# PDB2019.net
KiCad netlist of a schematic drawn in EAGLE
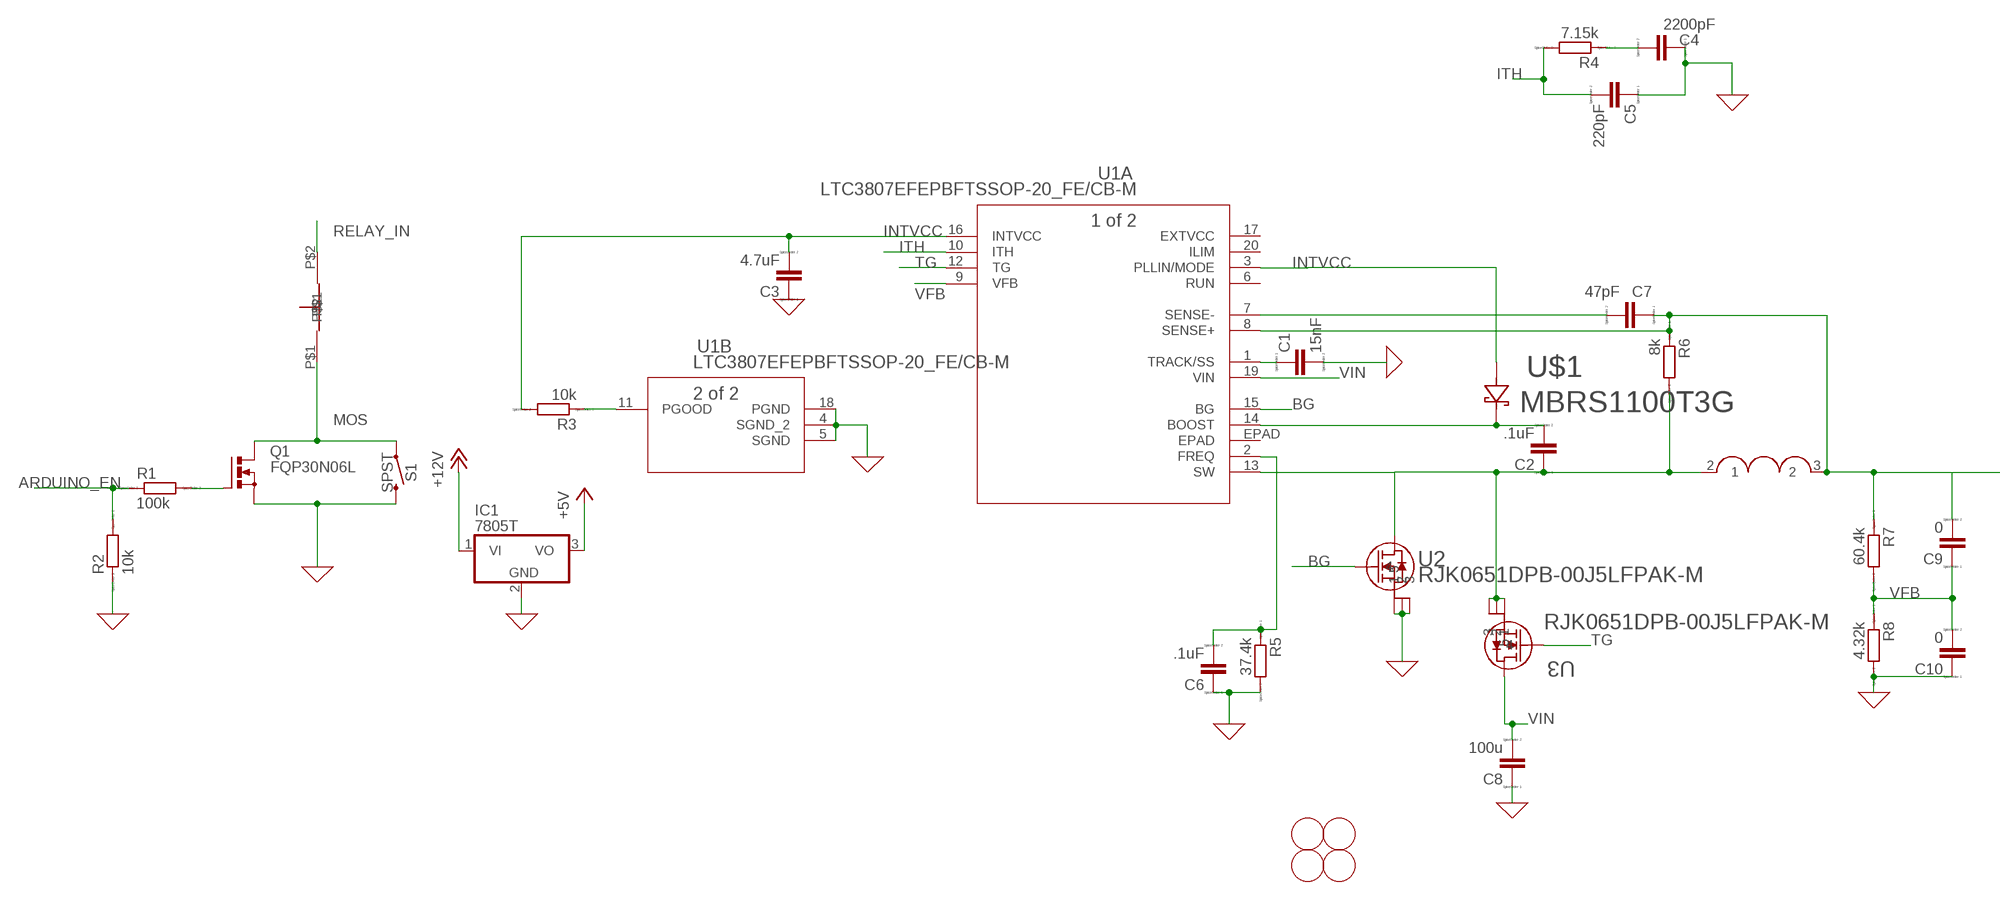
[diagram p0: schematic, sheet 1, part 1 of 2]
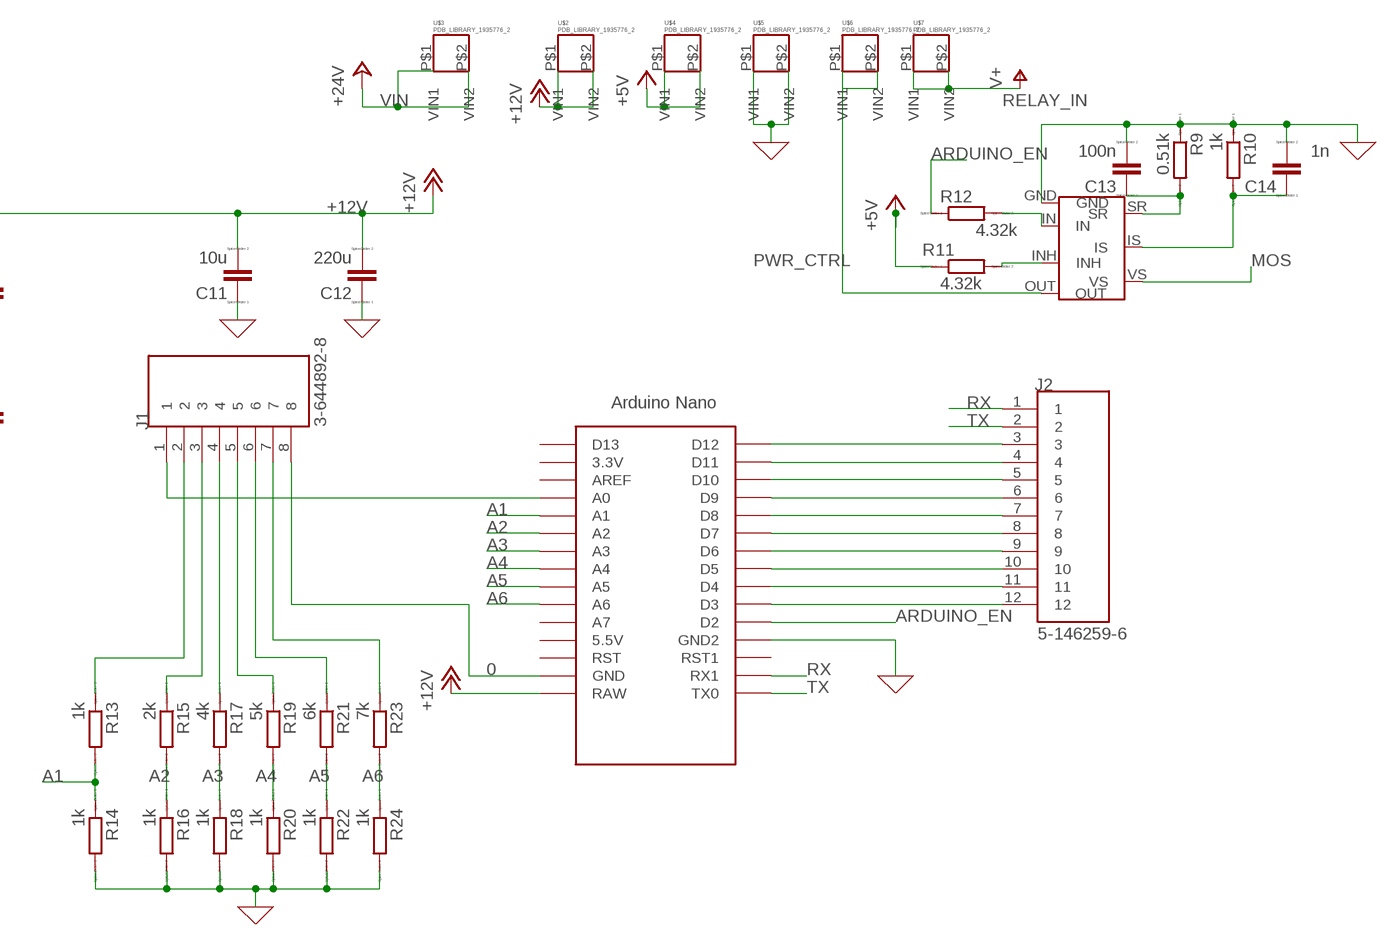
[diagram p1: schematic, sheet 1, part 2 of 2]

(export (version "E")
  (design (tool "Eeschema 10.0.6"))
  (components
    (comp (ref "C1")
      (value "15nF")
      (footprint "eagle-import:C1206")
      (libsource (lib "eagle-import") (part "CC1206"))
    )
    (comp (ref "C2")
      (value ".1uF")
      (footprint "eagle-import:C1206")
      (libsource (lib "eagle-import") (part "CC1206"))
    )
    (comp (ref "C3")
      (value "4.7uF")
      (footprint "eagle-import:C1206")
      (libsource (lib "eagle-import") (part "CC1206"))
    )
    (comp (ref "C4")
      (value "2200pF")
      (footprint "eagle-import:C1206")
      (libsource (lib "eagle-import") (part "CC1206"))
    )
    (comp (ref "C5")
      (value "220pF")
      (footprint "eagle-import:C1206")
      (libsource (lib "eagle-import") (part "CC1206"))
    )
    (comp (ref "C6")
      (value ".1uF")
      (footprint "eagle-import:C1206")
      (libsource (lib "eagle-import") (part "CC1206"))
    )
    (comp (ref "C7")
      (value "47pF")
      (footprint "eagle-import:C1206")
      (libsource (lib "eagle-import") (part "CC1206"))
    )
    (comp (ref "C8")
      (value "100u")
      (footprint "eagle-import:C1206")
      (libsource (lib "eagle-import") (part "CC1206"))
    )
    (comp (ref "C9")
      (value "0")
      (footprint "eagle-import:C1206")
      (libsource (lib "eagle-import") (part "CC1206"))
    )
    (comp (ref "C10")
      (value "0")
      (footprint "eagle-import:C1206")
      (libsource (lib "eagle-import") (part "CC1206"))
    )
    (comp (ref "C11")
      (value "10u")
      (footprint "eagle-import:C1206")
      (libsource (lib "eagle-import") (part "CC1206"))
    )
    (comp (ref "C12")
      (value "220u")
      (footprint "eagle-import:C1206")
      (libsource (lib "eagle-import") (part "CC1206"))
    )
    (comp (ref "C13")
      (value "100n")
      (footprint "eagle-import:C1206")
      (libsource (lib "eagle-import") (part "CC1206"))
    )
    (comp (ref "C14")
      (value "1n")
      (footprint "eagle-import:C1206")
      (libsource (lib "eagle-import") (part "CC1206"))
    )
    (comp (ref "IC1")
      (value "7805T")
      (footprint "eagle-import:TO220H")
      (libsource (lib "eagle-import") (part "78T05"))
    )
    (comp (ref "J1")
      (value "3-644892-8")
      (footprint "eagle-import:TE_3-644892-8")
      (fields (field (name "DIGI-KEY_PART_NUMBER") "A108137-ND") (field (name "MF") "TE Connectivity"))
      (libsource (lib "eagle-import") (part "3-644892-8"))
    )
    (comp (ref "J2")
      (value "5-146259-6")
      (footprint "eagle-import:TE_5-146259-6")
      (fields (field (name "DIGI-KEY_PART_NUMBER") "5-146259-6-ND") (field (name "MF") "TE Connectivity"))
      (libsource (lib "eagle-import") (part "5-146259-6"))
    )
    (comp (ref "L1")
      (value "INDUCT_MOONROCK")
      (footprint "eagle-import:INDUCT_MOONROCK")
      (libsource (lib "eagle-import") (part "INDUCT_MOONROCK"))
    )
    (comp (ref "Q1")
      (value "FQP30N06L")
      (footprint "eagle-import:TO220BV")
      (libsource (lib "eagle-import") (part "BUZ11BV"))
    )
    (comp (ref "R1")
      (value "100k")
      (footprint "eagle-import:0207_10")
      (libsource (lib "eagle-import") (part "R0207/10"))
    )
    (comp (ref "R2")
      (value "10k")
      (footprint "eagle-import:0207_10")
      (libsource (lib "eagle-import") (part "R0207/10"))
    )
    (comp (ref "R3")
      (value "10k")
      (footprint "eagle-import:0207_10")
      (libsource (lib "eagle-import") (part "R0207/10"))
    )
    (comp (ref "R4")
      (value "7.15k")
      (footprint "eagle-import:R1210")
      (libsource (lib "eagle-import") (part "RR1210"))
    )
    (comp (ref "R5")
      (value "37.4k")
      (footprint "eagle-import:R1210")
      (libsource (lib "eagle-import") (part "RR1210"))
    )
    (comp (ref "R6")
      (value "8k")
      (footprint "eagle-import:R1210")
      (libsource (lib "eagle-import") (part "RR1210"))
    )
    (comp (ref "R7")
      (value "60.4k")
      (footprint "eagle-import:R1210")
      (libsource (lib "eagle-import") (part "RR1210"))
    )
    (comp (ref "R8")
      (value "4.32k")
      (footprint "eagle-import:R1210")
      (libsource (lib "eagle-import") (part "RR1210"))
    )
    (comp (ref "R9")
      (value "0.51k")
      (footprint "eagle-import:R1210")
      (libsource (lib "eagle-import") (part "RR1210"))
    )
    (comp (ref "R10")
      (value "1k")
      (footprint "eagle-import:R1210")
      (libsource (lib "eagle-import") (part "RR1210"))
    )
    (comp (ref "R11")
      (value "4.32k")
      (footprint "eagle-import:R1210")
      (libsource (lib "eagle-import") (part "RR1210"))
    )
    (comp (ref "R12")
      (value "4.32k")
      (footprint "eagle-import:R1210")
      (libsource (lib "eagle-import") (part "RR1210"))
    )
    (comp (ref "R13")
      (value "1k")
      (footprint "eagle-import:R1210")
      (libsource (lib "eagle-import") (part "RR1210"))
    )
    (comp (ref "R14")
      (value "1k")
      (footprint "eagle-import:R1210")
      (libsource (lib "eagle-import") (part "RR1210"))
    )
    (comp (ref "R15")
      (value "2k")
      (footprint "eagle-import:R1210")
      (libsource (lib "eagle-import") (part "RR1210"))
    )
    (comp (ref "R16")
      (value "1k")
      (footprint "eagle-import:R1210")
      (libsource (lib "eagle-import") (part "RR1210"))
    )
    (comp (ref "R17")
      (value "4k")
      (footprint "eagle-import:R1210")
      (libsource (lib "eagle-import") (part "RR1210"))
    )
    (comp (ref "R18")
      (value "1k")
      (footprint "eagle-import:R1210")
      (libsource (lib "eagle-import") (part "RR1210"))
    )
    (comp (ref "R19")
      (value "5k")
      (footprint "eagle-import:R1210")
      (libsource (lib "eagle-import") (part "RR1210"))
    )
    (comp (ref "R20")
      (value "1k")
      (footprint "eagle-import:R1210")
      (libsource (lib "eagle-import") (part "RR1210"))
    )
    (comp (ref "R21")
      (value "6k")
      (footprint "eagle-import:R1210")
      (libsource (lib "eagle-import") (part "RR1210"))
    )
    (comp (ref "R22")
      (value "1k")
      (footprint "eagle-import:R1210")
      (libsource (lib "eagle-import") (part "RR1210"))
    )
    (comp (ref "R23")
      (value "7k")
      (footprint "eagle-import:R1210")
      (libsource (lib "eagle-import") (part "RR1210"))
    )
    (comp (ref "R24")
      (value "1k")
      (footprint "eagle-import:R1210")
      (libsource (lib "eagle-import") (part "RR1210"))
    )
    (comp (ref "S1")
      (value "SPST")
      (footprint "eagle-import:TACTILE_SWITCH_PTH_6.0MM_KIT")
      (libsource (lib "eagle-import") (part "MOMENTARY-SWITCH-SPST-PTH-6.0MM-KIT"))
    )
    (comp (ref "SW1")
      (value "SPSTSWITCH")
      (footprint "eagle-import:2HOLES")
      (libsource (lib "eagle-import") (part "SPSTSWITCH"))
    )
    (comp (ref "U$1")
      (value "MBRS1100T3G")
      (footprint "eagle-import:SMB")
      (libsource (lib "eagle-import") (part "MBRS1100T3G"))
    )
    (comp (ref "U$2")
      (value "PDB_LIBRARY_1935776_2")
      (footprint "eagle-import:PDB_LIBRARY_PT2,5_2-5,0-H_2")
      (libsource (lib "eagle-import") (part "PDB_LIBRARY_1935776_2"))
    )
    (comp (ref "U$3")
      (value "PDB_LIBRARY_1935776_2")
      (footprint "eagle-import:PDB_LIBRARY_PT2,5_2-5,0-H_2")
      (libsource (lib "eagle-import") (part "PDB_LIBRARY_1935776_2"))
    )
    (comp (ref "U$4")
      (value "PDB_LIBRARY_1935776_2")
      (footprint "eagle-import:PDB_LIBRARY_PT2,5_2-5,0-H_2")
      (libsource (lib "eagle-import") (part "PDB_LIBRARY_1935776_2"))
    )
    (comp (ref "U$5")
      (value "PDB_LIBRARY_1935776_2")
      (footprint "eagle-import:PDB_LIBRARY_PT2,5_2-5,0-H_2")
      (libsource (lib "eagle-import") (part "PDB_LIBRARY_1935776_2"))
    )
    (comp (ref "U$6")
      (value "PDB_LIBRARY_1935776_2")
      (footprint "eagle-import:PDB_LIBRARY_PT2,5_2-5,0-H_2")
      (libsource (lib "eagle-import") (part "PDB_LIBRARY_1935776_2"))
    )
    (comp (ref "U$7")
      (value "PDB_LIBRARY_1935776_2")
      (footprint "eagle-import:PDB_LIBRARY_PT2,5_2-5,0-H_2")
      (libsource (lib "eagle-import") (part "PDB_LIBRARY_1935776_2"))
    )
    (comp (ref "U$8")
      (value "NANO")
      (footprint "eagle-import:NANO")
      (libsource (lib "eagle-import") (part "NANO"))
    )
    (comp (ref "U$9")
      (value "MOUNTINGHOLES")
      (footprint "eagle-import:MOUNTINGHOLES")
      (libsource (lib "eagle-import") (part "MOUNTINGHOLES"))
    )
    (comp (ref "U1")
      (value "LTC3807EFEPBFTSSOP-20_FE/CB-M")
      (footprint "eagle-import:TSSOP-20_FE_CB-M")
      (fields (field (name "MANUFACTURER_PART_NUMBER") "LTC3807EFE#PBF"))
      (libsource (lib "eagle-import") (part "LTC3807EFEPBFTSSOP-20_FE/CB-M"))
    )
    (comp (ref "U2")
      (value "RJK0651DPB-00J5LFPAK-M")
      (footprint "eagle-import:LFPAK-M")
      (fields (field (name "MANUFACTURER_PART_NUMBER") "RJK0651DPB00#J5"))
      (libsource (lib "eagle-import") (part "RJK0651DPB-00J5LFPAK-M"))
    )
    (comp (ref "U3")
      (value "RJK0651DPB-00J5LFPAK-M")
      (footprint "eagle-import:LFPAK-M")
      (fields (field (name "MANUFACTURER_PART_NUMBER") "RJK0651DPB00#J5"))
      (libsource (lib "eagle-import") (part "RJK0651DPB-00J5LFPAK-M"))
    )
    (comp (ref "U4")
      (value "BTN8982TA")
      (footprint "eagle-import:TO-263-8")
      (libsource (lib "eagle-import") (part "BTN8982TA"))
    )
  )
  (nets
    (net (code "1") (name "+5V") (class "Default")
      (node (ref "IC1") (pin "3") (pinfunction "VO_3") (pintype "passive"))
      (node (ref "R11") (pin "1") (pinfunction "1_1") (pintype "passive"))
      (node (ref "U$4") (pin "P$1") (pinfunction "VIN1_P$1") (pintype "bidirectional"))
      (node (ref "U$4") (pin "P$2") (pinfunction "VIN2_P$2") (pintype "bidirectional"))
    )
    (net (code "2") (name "+12V") (class "Default")
      (node (ref "C11") (pin "2") (pinfunction "2_2") (pintype "passive"))
      (node (ref "C12") (pin "2") (pinfunction "2_2") (pintype "passive"))
      (node (ref "C7") (pin "1") (pinfunction "1_1") (pintype "passive"))
      (node (ref "C9") (pin "2") (pinfunction "2_2") (pintype "passive"))
      (node (ref "IC1") (pin "1") (pinfunction "VI_1") (pintype "input"))
      (node (ref "L1") (pin "3") (pinfunction "2_3") (pintype "bidirectional"))
      (node (ref "R6") (pin "1") (pinfunction "1_1") (pintype "passive"))
      (node (ref "R7") (pin "1") (pinfunction "1_1") (pintype "passive"))
      (node (ref "U$2") (pin "P$1") (pinfunction "VIN1_P$1") (pintype "bidirectional"))
      (node (ref "U$2") (pin "P$2") (pinfunction "VIN2_P$2") (pintype "bidirectional"))
      (node (ref "U$8") (pin "RAW") (pinfunction "RAW_RAW") (pintype "bidirectional"))
      (node (ref "U1") (pin "8") (pinfunction "SENSE+_8") (pintype "input"))
    )
    (net (code "3") (name "+24V") (class "Default")
      (node (ref "C8") (pin "2") (pinfunction "2_2") (pintype "passive"))
      (node (ref "U$3") (pin "P$1") (pinfunction "VIN1_P$1") (pintype "bidirectional"))
      (node (ref "U$3") (pin "P$2") (pinfunction "VIN2_P$2") (pintype "bidirectional"))
      (node (ref "U1") (pin "19") (pinfunction "VIN_19") (pintype "input"))
      (node (ref "U3") (pin "5") (pinfunction "5_5") (pintype "passive"))
    )
    (net (code "4") (name "/A1") (class "Default")
      (node (ref "R13") (pin "2") (pinfunction "2_2") (pintype "passive"))
      (node (ref "R14") (pin "1") (pinfunction "1_1") (pintype "passive"))
      (node (ref "U$8") (pin "A1") (pinfunction "A1_A1") (pintype "bidirectional"))
    )
    (net (code "5") (name "/A2") (class "Default")
      (node (ref "R15") (pin "2") (pinfunction "2_2") (pintype "passive"))
      (node (ref "R16") (pin "1") (pinfunction "1_1") (pintype "passive"))
      (node (ref "U$8") (pin "A2") (pinfunction "A2_A2") (pintype "bidirectional"))
    )
    (net (code "6") (name "/A3") (class "Default")
      (node (ref "R17") (pin "2") (pinfunction "2_2") (pintype "passive"))
      (node (ref "R18") (pin "1") (pinfunction "1_1") (pintype "passive"))
      (node (ref "U$8") (pin "A3") (pinfunction "A3_A3") (pintype "bidirectional"))
    )
    (net (code "7") (name "/A4") (class "Default")
      (node (ref "R19") (pin "2") (pinfunction "2_2") (pintype "passive"))
      (node (ref "R20") (pin "1") (pinfunction "1_1") (pintype "passive"))
      (node (ref "U$8") (pin "A4") (pinfunction "A4_A4") (pintype "bidirectional"))
    )
    (net (code "8") (name "/A5") (class "Default")
      (node (ref "R21") (pin "2") (pinfunction "2_2") (pintype "passive"))
      (node (ref "R22") (pin "1") (pinfunction "1_1") (pintype "passive"))
      (node (ref "U$8") (pin "A5") (pinfunction "A5_A5") (pintype "bidirectional"))
    )
    (net (code "9") (name "/A6") (class "Default")
      (node (ref "R23") (pin "2") (pinfunction "2_2") (pintype "passive"))
      (node (ref "R24") (pin "1") (pinfunction "1_1") (pintype "passive"))
      (node (ref "U$8") (pin "A6") (pinfunction "A6_A6") (pintype "bidirectional"))
    )
    (net (code "10") (name "/ARDUINO_EN") (class "Default")
      (node (ref "R1") (pin "1") (pinfunction "1_1") (pintype "passive"))
      (node (ref "R12") (pin "1") (pinfunction "1_1") (pintype "passive"))
      (node (ref "R2") (pin "2") (pinfunction "2_2") (pintype "passive"))
      (node (ref "U$8") (pin "D2") (pinfunction "D2_D2") (pintype "bidirectional"))
    )
    (net (code "11") (name "/BG") (class "Default")
      (node (ref "U1") (pin "15") (pinfunction "BG_15") (pintype "passive"))
      (node (ref "U2") (pin "4") (pinfunction "4_4") (pintype "passive"))
    )
    (net (code "12") (name "/INTVCC") (class "Default")
      (node (ref "C3") (pin "2") (pinfunction "2_2") (pintype "passive"))
      (node (ref "R3") (pin "2") (pinfunction "2_2") (pintype "passive"))
      (node (ref "U$1") (pin "2") (pinfunction "2_2") (pintype "passive"))
      (node (ref "U1") (pin "16") (pinfunction "INTVCC_16") (pintype "output"))
      (node (ref "U1") (pin "3") (pinfunction "PLLIN/MODE_3") (pintype "input"))
    )
    (net (code "13") (name "/ITH") (class "Default")
      (node (ref "C5") (pin "2") (pinfunction "2_2") (pintype "passive"))
      (node (ref "R4") (pin "2") (pinfunction "2_2") (pintype "passive"))
      (node (ref "U1") (pin "10") (pinfunction "ITH_10") (pintype "output"))
    )
    (net (code "14") (name "/MOS") (class "Default")
      (node (ref "Q1") (pin "D") (pinfunction "D_D") (pintype "passive"))
      (node (ref "S1") (pin "1") (pinfunction "1_1") (pintype "passive"))
      (node (ref "SW1") (pin "P$1") (pinfunction "P$1_P$1") (pintype "bidirectional"))
      (node (ref "U4") (pin "VS") (pinfunction "VS_VS") (pintype "bidirectional"))
    )
    (net (code "15") (name "/PWR_CTRL") (class "Default")
      (node (ref "U$6") (pin "P$1") (pinfunction "VIN1_P$1") (pintype "bidirectional"))
      (node (ref "U$6") (pin "P$2") (pinfunction "VIN2_P$2") (pintype "bidirectional"))
      (node (ref "U4") (pin "OUT") (pinfunction "OUT_OUT") (pintype "bidirectional"))
    )
    (net (code "16") (name "/RX") (class "Default")
      (node (ref "J2") (pin "1") (pinfunction "1_1") (pintype "passive"))
      (node (ref "U$8") (pin "RX1") (pinfunction "RX1_RX1") (pintype "bidirectional"))
    )
    (net (code "17") (name "/TG") (class "Default")
      (node (ref "U1") (pin "12") (pinfunction "TG_12") (pintype "output"))
      (node (ref "U3") (pin "4") (pinfunction "4_4") (pintype "passive"))
    )
    (net (code "18") (name "/TX") (class "Default")
      (node (ref "J2") (pin "2") (pinfunction "2_2") (pintype "passive"))
      (node (ref "U$8") (pin "TX0") (pinfunction "TX0_TX0") (pintype "bidirectional"))
    )
    (net (code "19") (name "/VFB") (class "Default")
      (node (ref "C10") (pin "2") (pinfunction "2_2") (pintype "passive"))
      (node (ref "C9") (pin "1") (pinfunction "1_1") (pintype "passive"))
      (node (ref "R7") (pin "2") (pinfunction "2_2") (pintype "passive"))
      (node (ref "R8") (pin "1") (pinfunction "1_1") (pintype "passive"))
      (node (ref "U1") (pin "9") (pinfunction "VFB_9") (pintype "output"))
    )
    (net (code "20") (name "GND") (class "Default")
      (node (ref "C1") (pin "2") (pinfunction "2_2") (pintype "passive"))
      (node (ref "C10") (pin "1") (pinfunction "1_1") (pintype "passive"))
      (node (ref "C11") (pin "1") (pinfunction "1_1") (pintype "passive"))
      (node (ref "C12") (pin "1") (pinfunction "1_1") (pintype "passive"))
      (node (ref "C13") (pin "2") (pinfunction "2_2") (pintype "passive"))
      (node (ref "C14") (pin "2") (pinfunction "2_2") (pintype "passive"))
      (node (ref "C3") (pin "1") (pinfunction "1_1") (pintype "passive"))
      (node (ref "C4") (pin "1") (pinfunction "1_1") (pintype "passive"))
      (node (ref "C5") (pin "1") (pinfunction "1_1") (pintype "passive"))
      (node (ref "C6") (pin "1") (pinfunction "1_1") (pintype "passive"))
      (node (ref "C8") (pin "1") (pinfunction "1_1") (pintype "passive"))
      (node (ref "IC1") (pin "2") (pinfunction "GND_2") (pintype "passive"))
      (node (ref "J1") (pin "8") (pinfunction "8_8") (pintype "passive"))
      (node (ref "Q1") (pin "S") (pinfunction "S_S") (pintype "passive"))
      (node (ref "R10") (pin "1") (pinfunction "1_1") (pintype "passive"))
      (node (ref "R14") (pin "2") (pinfunction "2_2") (pintype "passive"))
      (node (ref "R16") (pin "2") (pinfunction "2_2") (pintype "passive"))
      (node (ref "R18") (pin "2") (pinfunction "2_2") (pintype "passive"))
      (node (ref "R2") (pin "1") (pinfunction "1_1") (pintype "passive"))
      (node (ref "R20") (pin "2") (pinfunction "2_2") (pintype "passive"))
      (node (ref "R22") (pin "2") (pinfunction "2_2") (pintype "passive"))
      (node (ref "R24") (pin "2") (pinfunction "2_2") (pintype "passive"))
      (node (ref "R5") (pin "2") (pinfunction "2_2") (pintype "passive"))
      (node (ref "R8") (pin "2") (pinfunction "2_2") (pintype "passive"))
      (node (ref "R9") (pin "1") (pinfunction "1_1") (pintype "passive"))
      (node (ref "S1") (pin "3") (pinfunction "2_3") (pintype "passive"))
      (node (ref "U$5") (pin "P$1") (pinfunction "VIN1_P$1") (pintype "bidirectional"))
      (node (ref "U$5") (pin "P$2") (pinfunction "VIN2_P$2") (pintype "bidirectional"))
      (node (ref "U$8") (pin "GND") (pinfunction "GND_GND") (pintype "bidirectional"))
      (node (ref "U$8") (pin "GND1") (pinfunction "GND2_GND1") (pintype "bidirectional"))
      (node (ref "U1") (pin "18") (pinfunction "PGND_18") (pintype "power_in"))
      (node (ref "U1") (pin "4") (pinfunction "SGND_2_4") (pintype "power_in"))
      (node (ref "U1") (pin "5") (pinfunction "SGND_5") (pintype "power_in"))
      (node (ref "U2") (pin "1") (pinfunction "1_1") (pintype "passive"))
      (node (ref "U2") (pin "2") (pinfunction "2_2") (pintype "passive"))
      (node (ref "U2") (pin "3") (pinfunction "3_3") (pintype "passive"))
      (node (ref "U4") (pin "GND") (pinfunction "GND_GND") (pintype "bidirectional"))
    )
    (net (code "21") (name "Net-(C4-Pad2)") (class "Default")
      (node (ref "C4") (pin "2") (pinfunction "2_2") (pintype "passive"))
      (node (ref "R4") (pin "1") (pinfunction "1_1") (pintype "passive"))
    )
    (net (code "22") (name "Net-(C13-Pad1)") (class "Default")
      (node (ref "C13") (pin "1") (pinfunction "1_1") (pintype "passive"))
      (node (ref "R9") (pin "2") (pinfunction "2_2") (pintype "passive"))
      (node (ref "U4") (pin "SR") (pinfunction "SR_SR") (pintype "bidirectional"))
    )
    (net (code "23") (name "Net-(C14-Pad1)") (class "Default")
      (node (ref "C14") (pin "1") (pinfunction "1_1") (pintype "passive"))
      (node (ref "R10") (pin "2") (pinfunction "2_2") (pintype "passive"))
      (node (ref "U4") (pin "IS") (pinfunction "IS_IS") (pintype "bidirectional"))
    )
    (net (code "24") (name "Net-(J1-Pad1)") (class "Default")
      (node (ref "J1") (pin "1") (pinfunction "1_1") (pintype "passive"))
      (node (ref "U$8") (pin "A0") (pinfunction "A0_A0") (pintype "bidirectional"))
    )
    (net (code "25") (name "Net-(J1-Pad2)") (class "Default")
      (node (ref "J1") (pin "2") (pinfunction "2_2") (pintype "passive"))
      (node (ref "R13") (pin "1") (pinfunction "1_1") (pintype "passive"))
    )
    (net (code "26") (name "Net-(J1-Pad3)") (class "Default")
      (node (ref "J1") (pin "3") (pinfunction "3_3") (pintype "passive"))
      (node (ref "R15") (pin "1") (pinfunction "1_1") (pintype "passive"))
    )
    (net (code "27") (name "Net-(J1-Pad4)") (class "Default")
      (node (ref "J1") (pin "4") (pinfunction "4_4") (pintype "passive"))
      (node (ref "R17") (pin "1") (pinfunction "1_1") (pintype "passive"))
    )
    (net (code "28") (name "Net-(J1-Pad5)") (class "Default")
      (node (ref "J1") (pin "5") (pinfunction "5_5") (pintype "passive"))
      (node (ref "R19") (pin "1") (pinfunction "1_1") (pintype "passive"))
    )
    (net (code "29") (name "Net-(J1-Pad6)") (class "Default")
      (node (ref "J1") (pin "6") (pinfunction "6_6") (pintype "passive"))
      (node (ref "R21") (pin "1") (pinfunction "1_1") (pintype "passive"))
    )
    (net (code "30") (name "Net-(J1-Pad7)") (class "Default")
      (node (ref "J1") (pin "7") (pinfunction "7_7") (pintype "passive"))
      (node (ref "R23") (pin "1") (pinfunction "1_1") (pintype "passive"))
    )
    (net (code "31") (name "Net-(J2-Pad3)") (class "Default")
      (node (ref "J2") (pin "3") (pinfunction "3_3") (pintype "passive"))
      (node (ref "U$8") (pin "D12") (pinfunction "D12_D12") (pintype "bidirectional"))
    )
    (net (code "32") (name "Net-(J2-Pad4)") (class "Default")
      (node (ref "J2") (pin "4") (pinfunction "4_4") (pintype "passive"))
      (node (ref "U$8") (pin "D11") (pinfunction "D11_D11") (pintype "bidirectional"))
    )
    (net (code "33") (name "Net-(J2-Pad5)") (class "Default")
      (node (ref "J2") (pin "5") (pinfunction "5_5") (pintype "passive"))
      (node (ref "U$8") (pin "D10") (pinfunction "D10_D10") (pintype "bidirectional"))
    )
    (net (code "34") (name "Net-(J2-Pad6)") (class "Default")
      (node (ref "J2") (pin "6") (pinfunction "6_6") (pintype "passive"))
      (node (ref "U$8") (pin "D9") (pinfunction "D9_D9") (pintype "bidirectional"))
    )
    (net (code "35") (name "Net-(J2-Pad7)") (class "Default")
      (node (ref "J2") (pin "7") (pinfunction "7_7") (pintype "passive"))
      (node (ref "U$8") (pin "D8") (pinfunction "D8_D8") (pintype "bidirectional"))
    )
    (net (code "36") (name "Net-(J2-Pad8)") (class "Default")
      (node (ref "J2") (pin "8") (pinfunction "8_8") (pintype "passive"))
      (node (ref "U$8") (pin "D7") (pinfunction "D7_D7") (pintype "bidirectional"))
    )
    (net (code "37") (name "Net-(J2-Pad9)") (class "Default")
      (node (ref "J2") (pin "9") (pinfunction "9_9") (pintype "passive"))
      (node (ref "U$8") (pin "D6") (pinfunction "D6_D6") (pintype "bidirectional"))
    )
    (net (code "38") (name "Net-(J2-Pad10)") (class "Default")
      (node (ref "J2") (pin "10") (pinfunction "10_10") (pintype "passive"))
      (node (ref "U$8") (pin "D5") (pinfunction "D5_D5") (pintype "bidirectional"))
    )
    (net (code "39") (name "Net-(J2-Pad11)") (class "Default")
      (node (ref "J2") (pin "11") (pinfunction "11_11") (pintype "passive"))
      (node (ref "U$8") (pin "D4") (pinfunction "D4_D4") (pintype "bidirectional"))
    )
    (net (code "40") (name "Net-(J2-Pad12)") (class "Default")
      (node (ref "J2") (pin "12") (pinfunction "12_12") (pintype "passive"))
      (node (ref "U$8") (pin "D3") (pinfunction "D3_D3") (pintype "bidirectional"))
    )
    (net (code "41") (name "Net-(L1-1)") (class "Default")
      (node (ref "C2") (pin "1") (pinfunction "1_1") (pintype "passive"))
      (node (ref "L1") (pin "2") (pinfunction "1_2") (pintype "bidirectional"))
      (node (ref "R6") (pin "2") (pinfunction "2_2") (pintype "passive"))
      (node (ref "U1") (pin "13") (pinfunction "SW_13") (pintype "passive"))
      (node (ref "U2") (pin "5") (pinfunction "5_5") (pintype "passive"))
      (node (ref "U3") (pin "1") (pinfunction "1_1") (pintype "passive"))
      (node (ref "U3") (pin "2") (pinfunction "2_2") (pintype "passive"))
      (node (ref "U3") (pin "3") (pinfunction "3_3") (pintype "passive"))
    )
    (net (code "42") (name "Net-(Q1-PadG)") (class "Default")
      (node (ref "Q1") (pin "G") (pinfunction "G_G") (pintype "passive"))
      (node (ref "R1") (pin "2") (pinfunction "2_2") (pintype "passive"))
    )
    (net (code "43") (name "Net-(R11-Pad2)") (class "Default")
      (node (ref "R11") (pin "2") (pinfunction "2_2") (pintype "passive"))
      (node (ref "U4") (pin "INH") (pinfunction "INH_INH") (pintype "bidirectional"))
    )
    (net (code "44") (name "Net-(R12-Pad2)") (class "Default")
      (node (ref "R12") (pin "2") (pinfunction "2_2") (pintype "passive"))
      (node (ref "U4") (pin "IN") (pinfunction "IN_IN") (pintype "bidirectional"))
    )
    (net (code "45") (name "Net-(U1A-BOOST)") (class "Default")
      (node (ref "C2") (pin "2") (pinfunction "2_2") (pintype "passive"))
      (node (ref "U$1") (pin "1") (pinfunction "1_1") (pintype "passive"))
      (node (ref "U1") (pin "14") (pinfunction "BOOST_14") (pintype "passive"))
    )
    (net (code "46") (name "Net-(U1A-FREQ)") (class "Default")
      (node (ref "C6") (pin "2") (pinfunction "2_2") (pintype "passive"))
      (node (ref "R5") (pin "1") (pinfunction "1_1") (pintype "passive"))
      (node (ref "U1") (pin "2") (pinfunction "FREQ_2") (pintype "passive"))
    )
    (net (code "47") (name "Net-(U1A-SENSE-)") (class "Default")
      (node (ref "C7") (pin "2") (pinfunction "2_2") (pintype "passive"))
      (node (ref "U1") (pin "7") (pinfunction "SENSE-_7") (pintype "input"))
    )
    (net (code "48") (name "Net-(U1A-TRACK{slash}SS)") (class "Default")
      (node (ref "C1") (pin "1") (pinfunction "1_1") (pintype "passive"))
      (node (ref "U1") (pin "1") (pinfunction "TRACK/SS_1") (pintype "input"))
    )
    (net (code "49") (name "Net-(U1B-PGOOD)") (class "Default")
      (node (ref "R3") (pin "1") (pinfunction "1_1") (pintype "passive"))
      (node (ref "U1") (pin "11") (pinfunction "PGOOD_11") (pintype "output"))
    )
    (net (code "50") (name "V+") (class "Default")
      (node (ref "SW1") (pin "P$2") (pinfunction "P$2_P$2") (pintype "bidirectional"))
      (node (ref "U$7") (pin "P$1") (pinfunction "VIN1_P$1") (pintype "bidirectional"))
      (node (ref "U$7") (pin "P$2") (pinfunction "VIN2_P$2") (pintype "bidirectional"))
    )
    (net (code "51") (name "unconnected-(U$8-5.5V-Pad5V)") (class "Default")
      (node (ref "U$8") (pin "5V") (pinfunction "5.5V_5V") (pintype "bidirectional"))
    )
    (net (code "52") (name "unconnected-(U$8-Pad3.3V)") (class "Default")
      (node (ref "U$8") (pin "3.3V") (pinfunction "3.3V_3.3V") (pintype "bidirectional"))
    )
    (net (code "53") (name "unconnected-(U$8-PadA7)") (class "Default")
      (node (ref "U$8") (pin "A7") (pinfunction "A7_A7") (pintype "bidirectional"))
    )
    (net (code "54") (name "unconnected-(U$8-PadAREF)") (class "Default")
      (node (ref "U$8") (pin "AREF") (pinfunction "AREF_AREF") (pintype "bidirectional"))
    )
    (net (code "55") (name "unconnected-(U$8-PadD13)") (class "Default")
      (node (ref "U$8") (pin "D13") (pinfunction "D13_D13") (pintype "bidirectional"))
    )
    (net (code "56") (name "unconnected-(U$8-PadICSP1)") (class "Default")
      (node (ref "U$8") (pin "ICSP1") (pinfunction "ICSP1_ICSP1") (pintype "bidirectional"))
    )
    (net (code "57") (name "unconnected-(U$8-PadICSP2)") (class "Default")
      (node (ref "U$8") (pin "ICSP2") (pinfunction "ICSP2_ICSP2") (pintype "bidirectional"))
    )
    (net (code "58") (name "unconnected-(U$8-PadICSP3)") (class "Default")
      (node (ref "U$8") (pin "ICSP3") (pinfunction "ICSP3_ICSP3") (pintype "bidirectional"))
    )
    (net (code "59") (name "unconnected-(U$8-PadICSP4)") (class "Default")
      (node (ref "U$8") (pin "ICSP4") (pinfunction "ICSP4_ICSP4") (pintype "bidirectional"))
    )
    (net (code "60") (name "unconnected-(U$8-PadICSP5)") (class "Default")
      (node (ref "U$8") (pin "ICSP5") (pinfunction "ICSP5_ICSP5") (pintype "bidirectional"))
    )
    (net (code "61") (name "unconnected-(U$8-PadICSP6)") (class "Default")
      (node (ref "U$8") (pin "ICSP6") (pinfunction "ICSP6_ICSP6") (pintype "bidirectional"))
    )
    (net (code "62") (name "unconnected-(U$8-PadRST)") (class "Default")
      (node (ref "U$8") (pin "RST") (pinfunction "RST_RST") (pintype "bidirectional"))
    )
    (net (code "63") (name "unconnected-(U$8-PadRST1)") (class "Default")
      (node (ref "U$8") (pin "RST1") (pinfunction "RST1_RST1") (pintype "bidirectional"))
    )
    (net (code "64") (name "unconnected-(U1-PadEPAD)") (class "Default")
      (node (ref "U1") (pin "EPAD") (pinfunction "EPAD_EPAD") (pintype "passive"))
    )
    (net (code "65") (name "unconnected-(U1A-EXTVCC-Pad17)") (class "Default")
      (node (ref "U1") (pin "17") (pinfunction "EXTVCC_17") (pintype "input"))
    )
    (net (code "66") (name "unconnected-(U1A-ILIM-Pad20)") (class "Default")
      (node (ref "U1") (pin "20") (pinfunction "ILIM_20") (pintype "input"))
    )
    (net (code "67") (name "unconnected-(U1A-RUN-Pad6)") (class "Default")
      (node (ref "U1") (pin "6") (pinfunction "RUN_6") (pintype "input"))
    )
  )
)
